# LogicLab.net
KiCad netlist of a schematic drawn in EAGLE
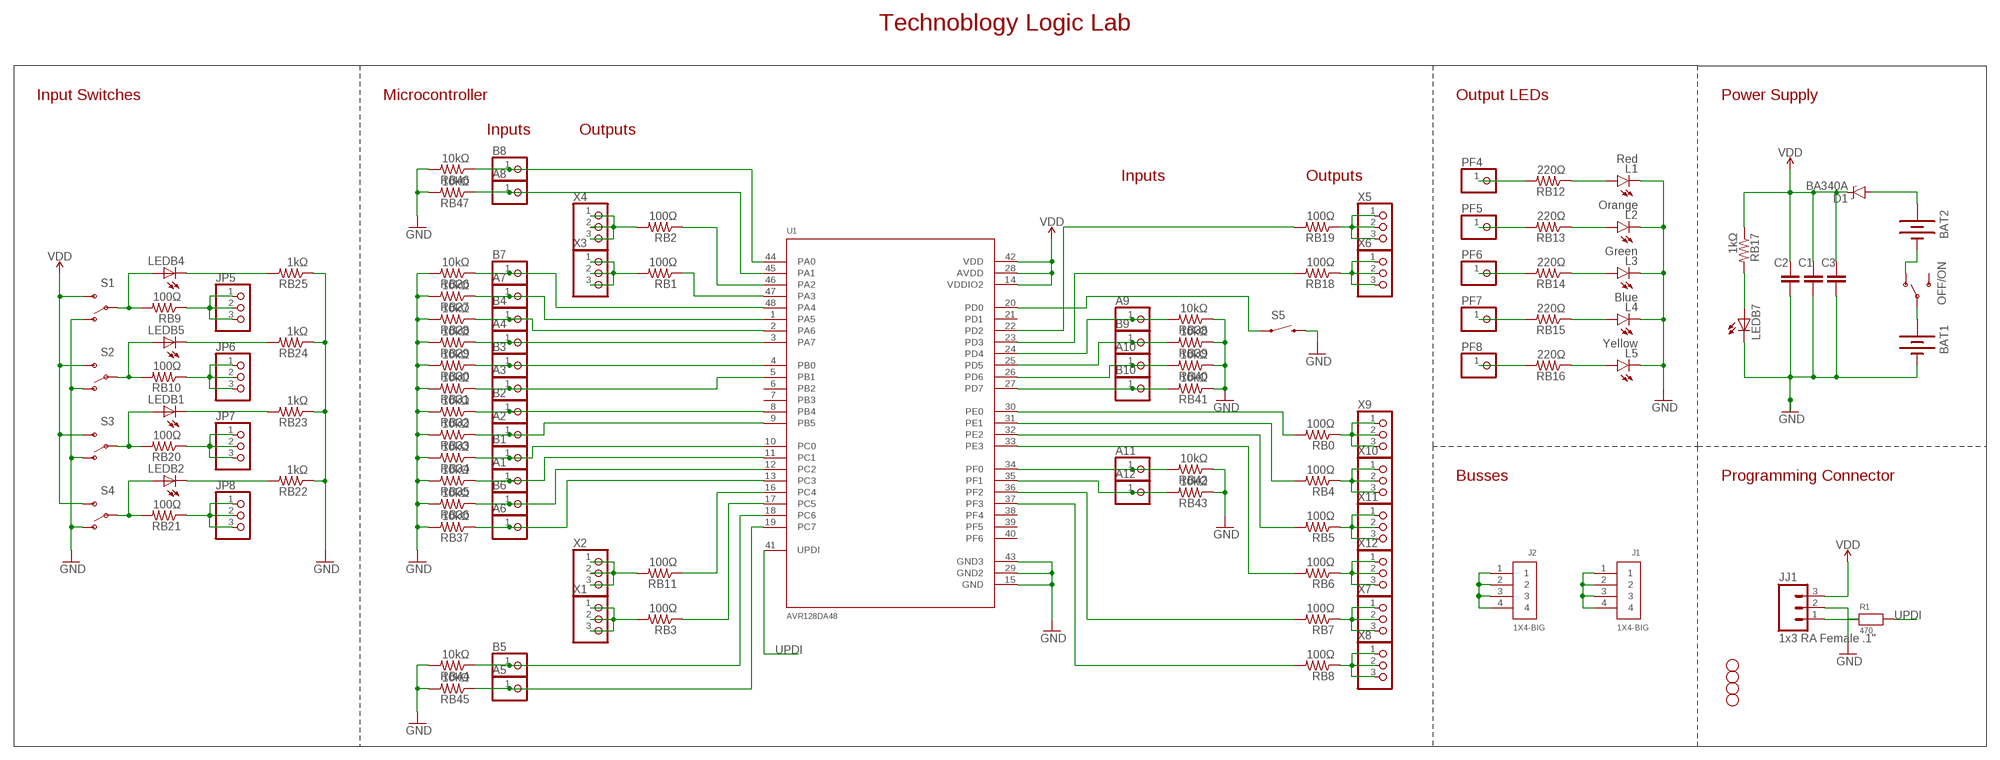
[diagram p0: schematic, sheet 1]

(export (version "E")
  (design (tool "Eeschema 10.0.6"))
  (components
    (comp (ref "A1")
      (value "PINHD-1X1")
      (footprint "eagle-import:1X01")
      (libsource (lib "eagle-import") (part "PINHD-1X1"))
    )
    (comp (ref "A2")
      (value "PINHD-1X1")
      (footprint "eagle-import:1X01")
      (libsource (lib "eagle-import") (part "PINHD-1X1"))
    )
    (comp (ref "A3")
      (value "PINHD-1X1")
      (footprint "eagle-import:1X01")
      (libsource (lib "eagle-import") (part "PINHD-1X1"))
    )
    (comp (ref "A4")
      (value "PINHD-1X1")
      (footprint "eagle-import:1X01")
      (libsource (lib "eagle-import") (part "PINHD-1X1"))
    )
    (comp (ref "A5")
      (value "PINHD-1X1")
      (footprint "eagle-import:1X01")
      (libsource (lib "eagle-import") (part "PINHD-1X1"))
    )
    (comp (ref "A6")
      (value "PINHD-1X1")
      (footprint "eagle-import:1X01")
      (libsource (lib "eagle-import") (part "PINHD-1X1"))
    )
    (comp (ref "A7")
      (value "PINHD-1X1")
      (footprint "eagle-import:1X01")
      (libsource (lib "eagle-import") (part "PINHD-1X1"))
    )
    (comp (ref "A8")
      (value "PINHD-1X1")
      (footprint "eagle-import:1X01")
      (libsource (lib "eagle-import") (part "PINHD-1X1"))
    )
    (comp (ref "A9")
      (value "PINHD-1X1")
      (footprint "eagle-import:1X01")
      (libsource (lib "eagle-import") (part "PINHD-1X1"))
    )
    (comp (ref "A10")
      (value "PINHD-1X1")
      (footprint "eagle-import:1X01")
      (libsource (lib "eagle-import") (part "PINHD-1X1"))
    )
    (comp (ref "A11")
      (value "PINHD-1X1")
      (footprint "eagle-import:1X01")
      (libsource (lib "eagle-import") (part "PINHD-1X1"))
    )
    (comp (ref "A12")
      (value "PINHD-1X1")
      (footprint "eagle-import:1X01")
      (libsource (lib "eagle-import") (part "PINHD-1X1"))
    )
    (comp (ref "B1")
      (value "PINHD-1X1")
      (footprint "eagle-import:1X01")
      (libsource (lib "eagle-import") (part "PINHD-1X1"))
    )
    (comp (ref "B2")
      (value "PINHD-1X1")
      (footprint "eagle-import:1X01")
      (libsource (lib "eagle-import") (part "PINHD-1X1"))
    )
    (comp (ref "B3")
      (value "PINHD-1X1")
      (footprint "eagle-import:1X01")
      (libsource (lib "eagle-import") (part "PINHD-1X1"))
    )
    (comp (ref "B4")
      (value "PINHD-1X1")
      (footprint "eagle-import:1X01")
      (libsource (lib "eagle-import") (part "PINHD-1X1"))
    )
    (comp (ref "B5")
      (value "PINHD-1X1")
      (footprint "eagle-import:1X01")
      (libsource (lib "eagle-import") (part "PINHD-1X1"))
    )
    (comp (ref "B6")
      (value "PINHD-1X1")
      (footprint "eagle-import:1X01")
      (libsource (lib "eagle-import") (part "PINHD-1X1"))
    )
    (comp (ref "B7")
      (value "PINHD-1X1")
      (footprint "eagle-import:1X01")
      (libsource (lib "eagle-import") (part "PINHD-1X1"))
    )
    (comp (ref "B8")
      (value "PINHD-1X1")
      (footprint "eagle-import:1X01")
      (libsource (lib "eagle-import") (part "PINHD-1X1"))
    )
    (comp (ref "B9")
      (value "PINHD-1X1")
      (footprint "eagle-import:1X01")
      (libsource (lib "eagle-import") (part "PINHD-1X1"))
    )
    (comp (ref "B10")
      (value "PINHD-1X1")
      (footprint "eagle-import:1X01")
      (libsource (lib "eagle-import") (part "PINHD-1X1"))
    )
    (comp (ref "BAT1")
      (value "BATTERYAAA-KIT")
      (footprint "eagle-import:BATTERY-AAA-KIT")
      (libsource (lib "eagle-import") (part "BATTERYAAA-KIT"))
    )
    (comp (ref "BAT2")
      (value "BATTERYAAA-KIT")
      (footprint "eagle-import:BATTERY-AAA-KIT")
      (libsource (lib "eagle-import") (part "BATTERYAAA-KIT"))
    )
    (comp (ref "C1")
      (value "100n")
      (footprint "eagle-import:0805")
      (libsource (lib "eagle-import") (part "CAP0805"))
    )
    (comp (ref "C2")
      (value "100n")
      (footprint "eagle-import:0805")
      (libsource (lib "eagle-import") (part "CAP0805"))
    )
    (comp (ref "C3")
      (value "10uF")
      (footprint "eagle-import:0805")
      (libsource (lib "eagle-import") (part "CAP0805"))
    )
    (comp (ref "D1")
      (value "BA340A")
      (footprint "eagle-import:SMA-DIODE")
      (libsource (lib "eagle-import") (part "B340A"))
    )
    (comp (ref "J1")
      (value "1X4-BIG")
      (footprint "eagle-import:1X04-BIG")
      (libsource (lib "eagle-import") (part "1X4-BIG"))
    )
    (comp (ref "J2")
      (value "1X4-BIG")
      (footprint "eagle-import:1X04-BIG")
      (libsource (lib "eagle-import") (part "1X4-BIG"))
    )
    (comp (ref "JJ1")
      (value "1x3 RA Female .1\"")
      (footprint "eagle-import:1X03_SMD_RA_FEMALE")
      (libsource (lib "eagle-import") (part "M03SMD_RA_FEMALE"))
    )
    (comp (ref "JP1")
      (value "STAND-OFF")
      (footprint "eagle-import:STAND-OFF")
      (libsource (lib "eagle-import") (part "STAND-OFF"))
    )
    (comp (ref "JP2")
      (value "STAND-OFF")
      (footprint "eagle-import:STAND-OFF")
      (libsource (lib "eagle-import") (part "STAND-OFF"))
    )
    (comp (ref "JP3")
      (value "STAND-OFF")
      (footprint "eagle-import:STAND-OFF")
      (libsource (lib "eagle-import") (part "STAND-OFF"))
    )
    (comp (ref "JP4")
      (value "STAND-OFF")
      (footprint "eagle-import:STAND-OFF")
      (libsource (lib "eagle-import") (part "STAND-OFF"))
    )
    (comp (ref "JP5")
      (value "PINHD-1X3")
      (footprint "eagle-import:1X03")
      (libsource (lib "eagle-import") (part "PINHD-1X3"))
    )
    (comp (ref "JP6")
      (value "PINHD-1X3")
      (footprint "eagle-import:1X03")
      (libsource (lib "eagle-import") (part "PINHD-1X3"))
    )
    (comp (ref "JP7")
      (value "PINHD-1X3")
      (footprint "eagle-import:1X03")
      (libsource (lib "eagle-import") (part "PINHD-1X3"))
    )
    (comp (ref "JP8")
      (value "PINHD-1X3")
      (footprint "eagle-import:1X03")
      (libsource (lib "eagle-import") (part "PINHD-1X3"))
    )
    (comp (ref "L1")
      (value "Red")
      (footprint "eagle-import:LED5MM")
      (libsource (lib "eagle-import") (part "LED5MM"))
    )
    (comp (ref "L2")
      (value "Orange")
      (footprint "eagle-import:LED5MM")
      (libsource (lib "eagle-import") (part "LED5MM"))
    )
    (comp (ref "L3")
      (value "Green")
      (footprint "eagle-import:LED5MM")
      (libsource (lib "eagle-import") (part "LED5MM"))
    )
    (comp (ref "L4")
      (value "Blue")
      (footprint "eagle-import:LED5MM")
      (libsource (lib "eagle-import") (part "LED5MM"))
    )
    (comp (ref "L5")
      (value "Yellow")
      (footprint "eagle-import:LED5MM")
      (libsource (lib "eagle-import") (part "LED5MM"))
    )
    (comp (ref "LEDB1")
      (value "LEDCHIPLED_0805")
      (footprint "eagle-import:CHIPLED_0805")
      (libsource (lib "eagle-import") (part "LEDCHIPLED_0805"))
    )
    (comp (ref "LEDB2")
      (value "LEDCHIPLED_0805")
      (footprint "eagle-import:CHIPLED_0805")
      (libsource (lib "eagle-import") (part "LEDCHIPLED_0805"))
    )
    (comp (ref "LEDB4")
      (value "LEDCHIPLED_0805")
      (footprint "eagle-import:CHIPLED_0805")
      (libsource (lib "eagle-import") (part "LEDCHIPLED_0805"))
    )
    (comp (ref "LEDB5")
      (value "LEDCHIPLED_0805")
      (footprint "eagle-import:CHIPLED_0805")
      (libsource (lib "eagle-import") (part "LEDCHIPLED_0805"))
    )
    (comp (ref "LEDB7")
      (value "LEDCHIPLED_0805")
      (footprint "eagle-import:CHIPLED_0805")
      (libsource (lib "eagle-import") (part "LEDCHIPLED_0805"))
    )
    (comp (ref "OFF/ON")
      (value "SWITCH-SPDTKIT")
      (footprint "eagle-import:SWITCH-SPDT_KIT")
      (libsource (lib "eagle-import") (part "SWITCH-SPDTKIT"))
    )
    (comp (ref "PF4")
      (value "PINHD-1X1")
      (footprint "eagle-import:1X01")
      (libsource (lib "eagle-import") (part "PINHD-1X1"))
    )
    (comp (ref "PF5")
      (value "PINHD-1X1")
      (footprint "eagle-import:1X01")
      (libsource (lib "eagle-import") (part "PINHD-1X1"))
    )
    (comp (ref "PF6")
      (value "PINHD-1X1")
      (footprint "eagle-import:1X01")
      (libsource (lib "eagle-import") (part "PINHD-1X1"))
    )
    (comp (ref "PF7")
      (value "PINHD-1X1")
      (footprint "eagle-import:1X01")
      (libsource (lib "eagle-import") (part "PINHD-1X1"))
    )
    (comp (ref "PF8")
      (value "PINHD-1X1")
      (footprint "eagle-import:1X01")
      (libsource (lib "eagle-import") (part "PINHD-1X1"))
    )
    (comp (ref "R1")
      (value "470")
      (footprint "eagle-import:_0805MP")
      (libsource (lib "eagle-import") (part "RESISTOR_0805MP"))
    )
    (comp (ref "RB0")
      (value "100Ω")
      (footprint "eagle-import:0805")
      (libsource (lib "eagle-import") (part "RESISTOR0805-RES"))
    )
    (comp (ref "RB1")
      (value "100Ω")
      (footprint "eagle-import:0805")
      (libsource (lib "eagle-import") (part "RESISTOR0805-RES"))
    )
    (comp (ref "RB2")
      (value "100Ω")
      (footprint "eagle-import:0805")
      (libsource (lib "eagle-import") (part "RESISTOR0805-RES"))
    )
    (comp (ref "RB3")
      (value "100Ω")
      (footprint "eagle-import:0805")
      (libsource (lib "eagle-import") (part "RESISTOR0805-RES"))
    )
    (comp (ref "RB4")
      (value "100Ω")
      (footprint "eagle-import:0805")
      (libsource (lib "eagle-import") (part "RESISTOR0805-RES"))
    )
    (comp (ref "RB5")
      (value "100Ω")
      (footprint "eagle-import:0805")
      (libsource (lib "eagle-import") (part "RESISTOR0805-RES"))
    )
    (comp (ref "RB6")
      (value "100Ω")
      (footprint "eagle-import:0805")
      (libsource (lib "eagle-import") (part "RESISTOR0805-RES"))
    )
    (comp (ref "RB7")
      (value "100Ω")
      (footprint "eagle-import:0805")
      (libsource (lib "eagle-import") (part "RESISTOR0805-RES"))
    )
    (comp (ref "RB8")
      (value "100Ω")
      (footprint "eagle-import:0805")
      (libsource (lib "eagle-import") (part "RESISTOR0805-RES"))
    )
    (comp (ref "RB9")
      (value "100Ω")
      (footprint "eagle-import:0805")
      (libsource (lib "eagle-import") (part "RESISTOR0805-RES"))
    )
    (comp (ref "RB10")
      (value "100Ω")
      (footprint "eagle-import:0805")
      (libsource (lib "eagle-import") (part "RESISTOR0805-RES"))
    )
    (comp (ref "RB11")
      (value "100Ω")
      (footprint "eagle-import:0805")
      (libsource (lib "eagle-import") (part "RESISTOR0805-RES"))
    )
    (comp (ref "RB12")
      (value "220Ω")
      (footprint "eagle-import:0805")
      (libsource (lib "eagle-import") (part "RESISTOR0805-RES"))
    )
    (comp (ref "RB13")
      (value "220Ω")
      (footprint "eagle-import:0805")
      (libsource (lib "eagle-import") (part "RESISTOR0805-RES"))
    )
    (comp (ref "RB14")
      (value "220Ω")
      (footprint "eagle-import:0805")
      (libsource (lib "eagle-import") (part "RESISTOR0805-RES"))
    )
    (comp (ref "RB15")
      (value "220Ω")
      (footprint "eagle-import:0805")
      (libsource (lib "eagle-import") (part "RESISTOR0805-RES"))
    )
    (comp (ref "RB16")
      (value "220Ω")
      (footprint "eagle-import:0805")
      (libsource (lib "eagle-import") (part "RESISTOR0805-RES"))
    )
    (comp (ref "RB17")
      (value "1kΩ")
      (footprint "eagle-import:0805")
      (libsource (lib "eagle-import") (part "RESISTOR0805-RES"))
    )
    (comp (ref "RB18")
      (value "100Ω")
      (footprint "eagle-import:0805")
      (libsource (lib "eagle-import") (part "RESISTOR0805-RES"))
    )
    (comp (ref "RB19")
      (value "100Ω")
      (footprint "eagle-import:0805")
      (libsource (lib "eagle-import") (part "RESISTOR0805-RES"))
    )
    (comp (ref "RB20")
      (value "100Ω")
      (footprint "eagle-import:0805")
      (libsource (lib "eagle-import") (part "RESISTOR0805-RES"))
    )
    (comp (ref "RB21")
      (value "100Ω")
      (footprint "eagle-import:0805")
      (libsource (lib "eagle-import") (part "RESISTOR0805-RES"))
    )
    (comp (ref "RB22")
      (value "1kΩ")
      (footprint "eagle-import:0805")
      (libsource (lib "eagle-import") (part "RESISTOR0805-RES"))
    )
    (comp (ref "RB23")
      (value "1kΩ")
      (footprint "eagle-import:0805")
      (libsource (lib "eagle-import") (part "RESISTOR0805-RES"))
    )
    (comp (ref "RB24")
      (value "1kΩ")
      (footprint "eagle-import:0805")
      (libsource (lib "eagle-import") (part "RESISTOR0805-RES"))
    )
    (comp (ref "RB25")
      (value "1kΩ")
      (footprint "eagle-import:0805")
      (libsource (lib "eagle-import") (part "RESISTOR0805-RES"))
    )
    (comp (ref "RB26")
      (value "10kΩ")
      (footprint "eagle-import:0805")
      (libsource (lib "eagle-import") (part "RESISTOR0805-RES"))
    )
    (comp (ref "RB27")
      (value "10kΩ")
      (footprint "eagle-import:0805")
      (libsource (lib "eagle-import") (part "RESISTOR0805-RES"))
    )
    (comp (ref "RB28")
      (value "10kΩ")
      (footprint "eagle-import:0805")
      (libsource (lib "eagle-import") (part "RESISTOR0805-RES"))
    )
    (comp (ref "RB29")
      (value "10kΩ")
      (footprint "eagle-import:0805")
      (libsource (lib "eagle-import") (part "RESISTOR0805-RES"))
    )
    (comp (ref "RB30")
      (value "10kΩ")
      (footprint "eagle-import:0805")
      (libsource (lib "eagle-import") (part "RESISTOR0805-RES"))
    )
    (comp (ref "RB31")
      (value "10kΩ")
      (footprint "eagle-import:0805")
      (libsource (lib "eagle-import") (part "RESISTOR0805-RES"))
    )
    (comp (ref "RB32")
      (value "10kΩ")
      (footprint "eagle-import:0805")
      (libsource (lib "eagle-import") (part "RESISTOR0805-RES"))
    )
    (comp (ref "RB33")
      (value "10kΩ")
      (footprint "eagle-import:0805")
      (libsource (lib "eagle-import") (part "RESISTOR0805-RES"))
    )
    (comp (ref "RB34")
      (value "10kΩ")
      (footprint "eagle-import:0805")
      (libsource (lib "eagle-import") (part "RESISTOR0805-RES"))
    )
    (comp (ref "RB35")
      (value "10kΩ")
      (footprint "eagle-import:0805")
      (libsource (lib "eagle-import") (part "RESISTOR0805-RES"))
    )
    (comp (ref "RB36")
      (value "10kΩ")
      (footprint "eagle-import:0805")
      (libsource (lib "eagle-import") (part "RESISTOR0805-RES"))
    )
    (comp (ref "RB37")
      (value "10kΩ")
      (footprint "eagle-import:0805")
      (libsource (lib "eagle-import") (part "RESISTOR0805-RES"))
    )
    (comp (ref "RB38")
      (value "10kΩ")
      (footprint "eagle-import:0805")
      (libsource (lib "eagle-import") (part "RESISTOR0805-RES"))
    )
    (comp (ref "RB39")
      (value "10kΩ")
      (footprint "eagle-import:0805")
      (libsource (lib "eagle-import") (part "RESISTOR0805-RES"))
    )
    (comp (ref "RB40")
      (value "10kΩ")
      (footprint "eagle-import:0805")
      (libsource (lib "eagle-import") (part "RESISTOR0805-RES"))
    )
    (comp (ref "RB41")
      (value "10kΩ")
      (footprint "eagle-import:0805")
      (libsource (lib "eagle-import") (part "RESISTOR0805-RES"))
    )
    (comp (ref "RB42")
      (value "10kΩ")
      (footprint "eagle-import:0805")
      (libsource (lib "eagle-import") (part "RESISTOR0805-RES"))
    )
    (comp (ref "RB43")
      (value "10kΩ")
      (footprint "eagle-import:0805")
      (libsource (lib "eagle-import") (part "RESISTOR0805-RES"))
    )
    (comp (ref "RB44")
      (value "10kΩ")
      (footprint "eagle-import:0805")
      (libsource (lib "eagle-import") (part "RESISTOR0805-RES"))
    )
    (comp (ref "RB45")
      (value "10kΩ")
      (footprint "eagle-import:0805")
      (libsource (lib "eagle-import") (part "RESISTOR0805-RES"))
    )
    (comp (ref "RB46")
      (value "10kΩ")
      (footprint "eagle-import:0805")
      (libsource (lib "eagle-import") (part "RESISTOR0805-RES"))
    )
    (comp (ref "RB47")
      (value "10kΩ")
      (footprint "eagle-import:0805")
      (libsource (lib "eagle-import") (part "RESISTOR0805-RES"))
    )
    (comp (ref "S1")
      (value "SWITCH-SPDTKIT")
      (footprint "eagle-import:SWITCH-SPDT_KIT")
      (libsource (lib "eagle-import") (part "SWITCH-SPDTKIT"))
    )
    (comp (ref "S2")
      (value "SWITCH-SPDTKIT")
      (footprint "eagle-import:SWITCH-SPDT_KIT")
      (libsource (lib "eagle-import") (part "SWITCH-SPDTKIT"))
    )
    (comp (ref "S3")
      (value "SWITCH-SPDTKIT")
      (footprint "eagle-import:SWITCH-SPDT_KIT")
      (libsource (lib "eagle-import") (part "SWITCH-SPDTKIT"))
    )
    (comp (ref "S4")
      (value "SWITCH-SPDTKIT")
      (footprint "eagle-import:SWITCH-SPDT_KIT")
      (libsource (lib "eagle-import") (part "SWITCH-SPDTKIT"))
    )
    (comp (ref "S5")
      (value "SWITCH-MOMENTARY-2SMD-4.6X2.8MM")
      (footprint "eagle-import:TACTILE_SWITCH_SMD_4.6X2.8MM")
      (libsource (lib "eagle-import") (part "SWITCH-MOMENTARY-2SMD-4.6X2.8MM"))
    )
    (comp (ref "U1")
      (value "AVR128DA48")
      (footprint "eagle-import:LQFP48")
      (fields (field (name "MANF") "NXP"))
      (libsource (lib "eagle-import") (part "AVR128DB48"))
    )
    (comp (ref "X1")
      (value "PINHD-1X3")
      (footprint "eagle-import:1X03")
      (libsource (lib "eagle-import") (part "PINHD-1X3"))
    )
    (comp (ref "X2")
      (value "PINHD-1X3")
      (footprint "eagle-import:1X03")
      (libsource (lib "eagle-import") (part "PINHD-1X3"))
    )
    (comp (ref "X3")
      (value "PINHD-1X3")
      (footprint "eagle-import:1X03")
      (libsource (lib "eagle-import") (part "PINHD-1X3"))
    )
    (comp (ref "X4")
      (value "PINHD-1X3")
      (footprint "eagle-import:1X03")
      (libsource (lib "eagle-import") (part "PINHD-1X3"))
    )
    (comp (ref "X5")
      (value "PINHD-1X3")
      (footprint "eagle-import:1X03")
      (libsource (lib "eagle-import") (part "PINHD-1X3"))
    )
    (comp (ref "X6")
      (value "PINHD-1X3")
      (footprint "eagle-import:1X03")
      (libsource (lib "eagle-import") (part "PINHD-1X3"))
    )
    (comp (ref "X7")
      (value "PINHD-1X3")
      (footprint "eagle-import:1X03")
      (libsource (lib "eagle-import") (part "PINHD-1X3"))
    )
    (comp (ref "X8")
      (value "PINHD-1X3")
      (footprint "eagle-import:1X03")
      (libsource (lib "eagle-import") (part "PINHD-1X3"))
    )
    (comp (ref "X9")
      (value "PINHD-1X3")
      (footprint "eagle-import:1X03")
      (libsource (lib "eagle-import") (part "PINHD-1X3"))
    )
    (comp (ref "X10")
      (value "PINHD-1X3")
      (footprint "eagle-import:1X03")
      (libsource (lib "eagle-import") (part "PINHD-1X3"))
    )
    (comp (ref "X11")
      (value "PINHD-1X3")
      (footprint "eagle-import:1X03")
      (libsource (lib "eagle-import") (part "PINHD-1X3"))
    )
    (comp (ref "X12")
      (value "PINHD-1X3")
      (footprint "eagle-import:1X03")
      (libsource (lib "eagle-import") (part "PINHD-1X3"))
    )
  )
  (nets
    (net (code "1") (name "/UPDI") (class "Default")
      (node (ref "R1") (pin "2") (pinfunction "2_2") (pintype "passive"))
      (node (ref "U1") (pin "41") (pinfunction "UPDI_41") (pintype "bidirectional"))
    )
    (net (code "2") (name "GND") (class "Default")
      (node (ref "BAT1") (pin "GND@1") (pinfunction "-_GND@1") (pintype "power_in"))
      (node (ref "C1") (pin "2") (pinfunction "2_2") (pintype "passive"))
      (node (ref "C2") (pin "2") (pinfunction "2_2") (pintype "passive"))
      (node (ref "C3") (pin "2") (pinfunction "2_2") (pintype "passive"))
      (node (ref "JJ1") (pin "2") (pinfunction "2_2") (pintype "passive"))
      (node (ref "L1") (pin "K") (pinfunction "C_K") (pintype "passive"))
      (node (ref "L2") (pin "K") (pinfunction "C_K") (pintype "passive"))
      (node (ref "L3") (pin "K") (pinfunction "C_K") (pintype "passive"))
      (node (ref "L4") (pin "K") (pinfunction "C_K") (pintype "passive"))
      (node (ref "L5") (pin "K") (pinfunction "C_K") (pintype "passive"))
      (node (ref "LEDB7") (pin "C") (pinfunction "C_C") (pintype "passive"))
      (node (ref "RB22") (pin "1") (pinfunction "1_1") (pintype "passive"))
      (node (ref "RB23") (pin "1") (pinfunction "1_1") (pintype "passive"))
      (node (ref "RB24") (pin "1") (pinfunction "1_1") (pintype "passive"))
      (node (ref "RB25") (pin "1") (pinfunction "1_1") (pintype "passive"))
      (node (ref "RB26") (pin "2") (pinfunction "2_2") (pintype "passive"))
      (node (ref "RB27") (pin "2") (pinfunction "2_2") (pintype "passive"))
      (node (ref "RB28") (pin "2") (pinfunction "2_2") (pintype "passive"))
      (node (ref "RB29") (pin "2") (pinfunction "2_2") (pintype "passive"))
      (node (ref "RB30") (pin "2") (pinfunction "2_2") (pintype "passive"))
      (node (ref "RB31") (pin "2") (pinfunction "2_2") (pintype "passive"))
      (node (ref "RB32") (pin "2") (pinfunction "2_2") (pintype "passive"))
      (node (ref "RB33") (pin "2") (pinfunction "2_2") (pintype "passive"))
      (node (ref "RB34") (pin "2") (pinfunction "2_2") (pintype "passive"))
      (node (ref "RB35") (pin "2") (pinfunction "2_2") (pintype "passive"))
      (node (ref "RB36") (pin "2") (pinfunction "2_2") (pintype "passive"))
      (node (ref "RB37") (pin "2") (pinfunction "2_2") (pintype "passive"))
      (node (ref "RB38") (pin "1") (pinfunction "1_1") (pintype "passive"))
      (node (ref "RB39") (pin "1") (pinfunction "1_1") (pintype "passive"))
      (node (ref "RB40") (pin "1") (pinfunction "1_1") (pintype "passive"))
      (node (ref "RB41") (pin "1") (pinfunction "1_1") (pintype "passive"))
      (node (ref "RB42") (pin "1") (pinfunction "1_1") (pintype "passive"))
      (node (ref "RB43") (pin "1") (pinfunction "1_1") (pintype "passive"))
      (node (ref "RB44") (pin "2") (pinfunction "2_2") (pintype "passive"))
      (node (ref "RB45") (pin "2") (pinfunction "2_2") (pintype "passive"))
      (node (ref "RB46") (pin "2") (pinfunction "2_2") (pintype "passive"))
      (node (ref "RB47") (pin "2") (pinfunction "2_2") (pintype "passive"))
      (node (ref "S1") (pin "1") (pinfunction "O_1") (pintype "passive"))
      (node (ref "S2") (pin "1") (pinfunction "O_1") (pintype "passive"))
      (node (ref "S3") (pin "1") (pinfunction "O_1") (pintype "passive"))
      (node (ref "S4") (pin "1") (pinfunction "O_1") (pintype "passive"))
      (node (ref "S5") (pin "3") (pinfunction "2_3") (pintype "passive"))
      (node (ref "S5") (pin "4") (pinfunction "2_4") (pintype "passive"))
      (node (ref "U1") (pin "15") (pinfunction "GND_15") (pintype "power_in"))
      (node (ref "U1") (pin "29") (pinfunction "GND2_29") (pintype "power_in"))
      (node (ref "U1") (pin "43") (pinfunction "GND3_43") (pintype "power_in"))
    )
    (net (code "3") (name "Net-(BAT1-+)") (class "Default")
      (node (ref "BAT1") (pin "PWR@1") (pinfunction "+_PWR@1") (pintype "power_in"))
      (node (ref "OFF/ON") (pin "2") (pinfunction "P_2") (pintype "passive"))
    )
    (net (code "4") (name "Net-(BAT2-+)") (class "Default")
      (node (ref "BAT2") (pin "PWR@1") (pinfunction "+_PWR@1") (pintype "power_in"))
      (node (ref "D1") (pin "A") (pinfunction "A_A") (pintype "passive"))
    )
    (net (code "5") (name "Net-(BAT2--)") (class "Default")
      (node (ref "BAT2") (pin "GND@1") (pinfunction "-_GND@1") (pintype "power_in"))
      (node (ref "OFF/ON") (pin "1") (pinfunction "O_1") (pintype "passive"))
    )
    (net (code "6") (name "Net-(J1-Pad1)") (class "Default")
      (node (ref "J1") (pin "1") (pinfunction "1_1") (pintype "bidirectional"))
      (node (ref "J1") (pin "2") (pinfunction "2_2") (pintype "bidirectional"))
      (node (ref "J1") (pin "3") (pinfunction "3_3") (pintype "bidirectional"))
      (node (ref "J1") (pin "4") (pinfunction "4_4") (pintype "bidirectional"))
    )
    (net (code "7") (name "Net-(J2-Pad1)") (class "Default")
      (node (ref "J2") (pin "1") (pinfunction "1_1") (pintype "bidirectional"))
      (node (ref "J2") (pin "2") (pinfunction "2_2") (pintype "bidirectional"))
      (node (ref "J2") (pin "3") (pinfunction "3_3") (pintype "bidirectional"))
      (node (ref "J2") (pin "4") (pinfunction "4_4") (pintype "bidirectional"))
    )
    (net (code "8") (name "Net-(JJ1-Pad1)") (class "Default")
      (node (ref "JJ1") (pin "1") (pinfunction "1_1") (pintype "passive"))
      (node (ref "R1") (pin "1") (pinfunction "1_1") (pintype "passive"))
    )
    (net (code "9") (name "Net-(JP5-Pad1)") (class "Default")
      (node (ref "JP5") (pin "1") (pinfunction "1_1") (pintype "passive"))
      (node (ref "JP5") (pin "2") (pinfunction "2_2") (pintype "passive"))
      (node (ref "JP5") (pin "3") (pinfunction "3_3") (pintype "passive"))
      (node (ref "RB9") (pin "1") (pinfunction "1_1") (pintype "passive"))
    )
    (net (code "10") (name "Net-(JP6-Pad1)") (class "Default")
      (node (ref "JP6") (pin "1") (pinfunction "1_1") (pintype "passive"))
      (node (ref "JP6") (pin "2") (pinfunction "2_2") (pintype "passive"))
      (node (ref "JP6") (pin "3") (pinfunction "3_3") (pintype "passive"))
      (node (ref "RB10") (pin "1") (pinfunction "1_1") (pintype "passive"))
    )
    (net (code "11") (name "Net-(JP7-Pad1)") (class "Default")
      (node (ref "JP7") (pin "1") (pinfunction "1_1") (pintype "passive"))
      (node (ref "JP7") (pin "2") (pinfunction "2_2") (pintype "passive"))
      (node (ref "JP7") (pin "3") (pinfunction "3_3") (pintype "passive"))
      (node (ref "RB20") (pin "1") (pinfunction "1_1") (pintype "passive"))
    )
    (net (code "12") (name "Net-(JP8-Pad1)") (class "Default")
      (node (ref "JP8") (pin "1") (pinfunction "1_1") (pintype "passive"))
      (node (ref "JP8") (pin "2") (pinfunction "2_2") (pintype "passive"))
      (node (ref "JP8") (pin "3") (pinfunction "3_3") (pintype "passive"))
      (node (ref "RB21") (pin "1") (pinfunction "1_1") (pintype "passive"))
    )
    (net (code "13") (name "Net-(L1-PadA)") (class "Default")
      (node (ref "L1") (pin "A") (pinfunction "A_A") (pintype "passive"))
      (node (ref "RB12") (pin "1") (pinfunction "1_1") (pintype "passive"))
    )
    (net (code "14") (name "Net-(L2-PadA)") (class "Default")
      (node (ref "L2") (pin "A") (pinfunction "A_A") (pintype "passive"))
      (node (ref "RB13") (pin "1") (pinfunction "1_1") (pintype "passive"))
    )
    (net (code "15") (name "Net-(L3-PadA)") (class "Default")
      (node (ref "L3") (pin "A") (pinfunction "A_A") (pintype "passive"))
      (node (ref "RB14") (pin "1") (pinfunction "1_1") (pintype "passive"))
    )
    (net (code "16") (name "Net-(L4-PadA)") (class "Default")
      (node (ref "L4") (pin "A") (pinfunction "A_A") (pintype "passive"))
      (node (ref "RB15") (pin "1") (pinfunction "1_1") (pintype "passive"))
    )
    (net (code "17") (name "Net-(L5-PadA)") (class "Default")
      (node (ref "L5") (pin "A") (pinfunction "A_A") (pintype "passive"))
      (node (ref "RB16") (pin "1") (pinfunction "1_1") (pintype "passive"))
    )
    (net (code "18") (name "Net-(LEDB1-PadC)") (class "Default")
      (node (ref "LEDB1") (pin "C") (pinfunction "C_C") (pintype "passive"))
      (node (ref "RB23") (pin "2") (pinfunction "2_2") (pintype "passive"))
    )
    (net (code "19") (name "Net-(LEDB2-PadC)") (class "Default")
      (node (ref "LEDB2") (pin "C") (pinfunction "C_C") (pintype "passive"))
      (node (ref "RB22") (pin "2") (pinfunction "2_2") (pintype "passive"))
    )
    (net (code "20") (name "Net-(LEDB4-PadC)") (class "Default")
      (node (ref "LEDB4") (pin "C") (pinfunction "C_C") (pintype "passive"))
      (node (ref "RB25") (pin "2") (pinfunction "2_2") (pintype "passive"))
    )
    (net (code "21") (name "Net-(LEDB5-PadC)") (class "Default")
      (node (ref "LEDB5") (pin "C") (pinfunction "C_C") (pintype "passive"))
      (node (ref "RB24") (pin "2") (pinfunction "2_2") (pintype "passive"))
    )
    (net (code "22") (name "Net-(LEDB7-PadA)") (class "Default")
      (node (ref "LEDB7") (pin "A") (pinfunction "A_A") (pintype "passive"))
      (node (ref "RB17") (pin "2") (pinfunction "2_2") (pintype "passive"))
    )
    (net (code "23") (name "Net-(PF4-Pad1)") (class "Default")
      (node (ref "PF4") (pin "1") (pinfunction "1_1") (pintype "passive"))
      (node (ref "RB12") (pin "2") (pinfunction "2_2") (pintype "passive"))
    )
    (net (code "24") (name "Net-(PF5-Pad1)") (class "Default")
      (node (ref "PF5") (pin "1") (pinfunction "1_1") (pintype "passive"))
      (node (ref "RB13") (pin "2") (pinfunction "2_2") (pintype "passive"))
    )
    (net (code "25") (name "Net-(PF6-Pad1)") (class "Default")
      (node (ref "PF6") (pin "1") (pinfunction "1_1") (pintype "passive"))
      (node (ref "RB14") (pin "2") (pinfunction "2_2") (pintype "passive"))
    )
    (net (code "26") (name "Net-(PF7-Pad1)") (class "Default")
      (node (ref "PF7") (pin "1") (pinfunction "1_1") (pintype "passive"))
      (node (ref "RB15") (pin "2") (pinfunction "2_2") (pintype "passive"))
    )
    (net (code "27") (name "Net-(PF8-Pad1)") (class "Default")
      (node (ref "PF8") (pin "1") (pinfunction "1_1") (pintype "passive"))
      (node (ref "RB16") (pin "2") (pinfunction "2_2") (pintype "passive"))
    )
    (net (code "28") (name "Net-(RB0-Pad1)") (class "Default")
      (node (ref "RB0") (pin "1") (pinfunction "1_1") (pintype "passive"))
      (node (ref "X9") (pin "1") (pinfunction "1_1") (pintype "passive"))
      (node (ref "X9") (pin "2") (pinfunction "2_2") (pintype "passive"))
      (node (ref "X9") (pin "3") (pinfunction "3_3") (pintype "passive"))
    )
    (net (code "29") (name "Net-(RB1-Pad2)") (class "Default")
      (node (ref "RB1") (pin "2") (pinfunction "2_2") (pintype "passive"))
      (node (ref "X3") (pin "1") (pinfunction "1_1") (pintype "passive"))
      (node (ref "X3") (pin "2") (pinfunction "2_2") (pintype "passive"))
      (node (ref "X3") (pin "3") (pinfunction "3_3") (pintype "passive"))
    )
    (net (code "30") (name "Net-(RB2-Pad2)") (class "Default")
      (node (ref "RB2") (pin "2") (pinfunction "2_2") (pintype "passive"))
      (node (ref "X4") (pin "1") (pinfunction "1_1") (pintype "passive"))
      (node (ref "X4") (pin "2") (pinfunction "2_2") (pintype "passive"))
      (node (ref "X4") (pin "3") (pinfunction "3_3") (pintype "passive"))
    )
    (net (code "31") (name "Net-(RB3-Pad2)") (class "Default")
      (node (ref "RB3") (pin "2") (pinfunction "2_2") (pintype "passive"))
      (node (ref "X1") (pin "1") (pinfunction "1_1") (pintype "passive"))
      (node (ref "X1") (pin "2") (pinfunction "2_2") (pintype "passive"))
      (node (ref "X1") (pin "3") (pinfunction "3_3") (pintype "passive"))
    )
    (net (code "32") (name "Net-(RB4-Pad1)") (class "Default")
      (node (ref "RB4") (pin "1") (pinfunction "1_1") (pintype "passive"))
      (node (ref "X10") (pin "1") (pinfunction "1_1") (pintype "passive"))
      (node (ref "X10") (pin "2") (pinfunction "2_2") (pintype "passive"))
      (node (ref "X10") (pin "3") (pinfunction "3_3") (pintype "passive"))
    )
    (net (code "33") (name "Net-(RB5-Pad1)") (class "Default")
      (node (ref "RB5") (pin "1") (pinfunction "1_1") (pintype "passive"))
      (node (ref "X11") (pin "1") (pinfunction "1_1") (pintype "passive"))
      (node (ref "X11") (pin "2") (pinfunction "2_2") (pintype "passive"))
      (node (ref "X11") (pin "3") (pinfunction "3_3") (pintype "passive"))
    )
    (net (code "34") (name "Net-(RB6-Pad1)") (class "Default")
      (node (ref "RB6") (pin "1") (pinfunction "1_1") (pintype "passive"))
      (node (ref "X12") (pin "1") (pinfunction "1_1") (pintype "passive"))
      (node (ref "X12") (pin "2") (pinfunction "2_2") (pintype "passive"))
      (node (ref "X12") (pin "3") (pinfunction "3_3") (pintype "passive"))
    )
    (net (code "35") (name "Net-(RB7-Pad1)") (class "Default")
      (node (ref "RB7") (pin "1") (pinfunction "1_1") (pintype "passive"))
      (node (ref "X7") (pin "1") (pinfunction "1_1") (pintype "passive"))
      (node (ref "X7") (pin "2") (pinfunction "2_2") (pintype "passive"))
      (node (ref "X7") (pin "3") (pinfunction "3_3") (pintype "passive"))
    )
    (net (code "36") (name "Net-(RB8-Pad1)") (class "Default")
      (node (ref "RB8") (pin "1") (pinfunction "1_1") (pintype "passive"))
      (node (ref "X8") (pin "1") (pinfunction "1_1") (pintype "passive"))
      (node (ref "X8") (pin "2") (pinfunction "2_2") (pintype "passive"))
      (node (ref "X8") (pin "3") (pinfunction "3_3") (pintype "passive"))
    )
    (net (code "37") (name "Net-(RB11-Pad2)") (class "Default")
      (node (ref "RB11") (pin "2") (pinfunction "2_2") (pintype "passive"))
      (node (ref "X2") (pin "1") (pinfunction "1_1") (pintype "passive"))
      (node (ref "X2") (pin "2") (pinfunction "2_2") (pintype "passive"))
      (node (ref "X2") (pin "3") (pinfunction "3_3") (pintype "passive"))
    )
    (net (code "38") (name "Net-(RB18-Pad1)") (class "Default")
      (node (ref "RB18") (pin "1") (pinfunction "1_1") (pintype "passive"))
      (node (ref "X6") (pin "1") (pinfunction "1_1") (pintype "passive"))
      (node (ref "X6") (pin "2") (pinfunction "2_2") (pintype "passive"))
      (node (ref "X6") (pin "3") (pinfunction "3_3") (pintype "passive"))
    )
    (net (code "39") (name "Net-(RB19-Pad1)") (class "Default")
      (node (ref "RB19") (pin "1") (pinfunction "1_1") (pintype "passive"))
      (node (ref "X5") (pin "1") (pinfunction "1_1") (pintype "passive"))
      (node (ref "X5") (pin "2") (pinfunction "2_2") (pintype "passive"))
      (node (ref "X5") (pin "3") (pinfunction "3_3") (pintype "passive"))
    )
    (net (code "40") (name "Net-(S1-P)") (class "Default")
      (node (ref "LEDB4") (pin "A") (pinfunction "A_A") (pintype "passive"))
      (node (ref "RB9") (pin "2") (pinfunction "2_2") (pintype "passive"))
      (node (ref "S1") (pin "2") (pinfunction "P_2") (pintype "passive"))
    )
    (net (code "41") (name "Net-(S2-P)") (class "Default")
      (node (ref "LEDB5") (pin "A") (pinfunction "A_A") (pintype "passive"))
      (node (ref "RB10") (pin "2") (pinfunction "2_2") (pintype "passive"))
      (node (ref "S2") (pin "2") (pinfunction "P_2") (pintype "passive"))
    )
    (net (code "42") (name "Net-(S3-P)") (class "Default")
      (node (ref "LEDB1") (pin "A") (pinfunction "A_A") (pintype "passive"))
      (node (ref "RB20") (pin "2") (pinfunction "2_2") (pintype "passive"))
      (node (ref "S3") (pin "2") (pinfunction "P_2") (pintype "passive"))
    )
    (net (code "43") (name "Net-(S4-P)") (class "Default")
      (node (ref "LEDB2") (pin "A") (pinfunction "A_A") (pintype "passive"))
      (node (ref "RB21") (pin "2") (pinfunction "2_2") (pintype "passive"))
      (node (ref "S4") (pin "2") (pinfunction "P_2") (pintype "passive"))
    )
    (net (code "44") (name "Net-(U1-PA0)") (class "Default")
      (node (ref "B8") (pin "1") (pinfunction "1_1") (pintype "passive"))
      (node (ref "RB46") (pin "1") (pinfunction "1_1") (pintype "passive"))
      (node (ref "U1") (pin "44") (pinfunction "PA0_44") (pintype "bidirectional"))
    )
    (net (code "45") (name "Net-(U1-PA1)") (class "Default")
      (node (ref "A8") (pin "1") (pinfunction "1_1") (pintype "passive"))
      (node (ref "RB47") (pin "1") (pinfunction "1_1") (pintype "passive"))
      (node (ref "U1") (pin "45") (pinfunction "PA1_45") (pintype "bidirectional"))
    )
    (net (code "46") (name "Net-(U1-PA2)") (class "Default")
      (node (ref "RB2") (pin "1") (pinfunction "1_1") (pintype "passive"))
      (node (ref "U1") (pin "46") (pinfunction "PA2_46") (pintype "bidirectional"))
    )
    (net (code "47") (name "Net-(U1-PA3)") (class "Default")
      (node (ref "RB1") (pin "1") (pinfunction "1_1") (pintype "passive"))
      (node (ref "U1") (pin "47") (pinfunction "PA3_47") (pintype "bidirectional"))
    )
    (net (code "48") (name "Net-(U1-PA4)") (class "Default")
      (node (ref "B7") (pin "1") (pinfunction "1_1") (pintype "passive"))
      (node (ref "RB26") (pin "1") (pinfunction "1_1") (pintype "passive"))
      (node (ref "U1") (pin "48") (pinfunction "PA4_48") (pintype "bidirectional"))
    )
    (net (code "49") (name "Net-(U1-PA5)") (class "Default")
      (node (ref "A7") (pin "1") (pinfunction "1_1") (pintype "passive"))
      (node (ref "RB27") (pin "1") (pinfunction "1_1") (pintype "passive"))
      (node (ref "U1") (pin "1") (pinfunction "PA5_1") (pintype "bidirectional"))
    )
    (net (code "50") (name "Net-(U1-PA6)") (class "Default")
      (node (ref "B4") (pin "1") (pinfunction "1_1") (pintype "passive"))
      (node (ref "RB28") (pin "1") (pinfunction "1_1") (pintype "passive"))
      (node (ref "U1") (pin "2") (pinfunction "PA6_2") (pintype "bidirectional"))
    )
    (net (code "51") (name "Net-(U1-PA7)") (class "Default")
      (node (ref "A4") (pin "1") (pinfunction "1_1") (pintype "passive"))
      (node (ref "RB29") (pin "1") (pinfunction "1_1") (pintype "passive"))
      (node (ref "U1") (pin "3") (pinfunction "PA7_3") (pintype "bidirectional"))
    )
    (net (code "52") (name "Net-(U1-PB0)") (class "Default")
      (node (ref "B3") (pin "1") (pinfunction "1_1") (pintype "passive"))
      (node (ref "RB30") (pin "1") (pinfunction "1_1") (pintype "passive"))
      (node (ref "U1") (pin "4") (pinfunction "PB0_4") (pintype "bidirectional"))
    )
    (net (code "53") (name "Net-(U1-PB1)") (class "Default")
      (node (ref "A3") (pin "1") (pinfunction "1_1") (pintype "passive"))
      (node (ref "RB31") (pin "1") (pinfunction "1_1") (pintype "passive"))
      (node (ref "U1") (pin "5") (pinfunction "PB1_5") (pintype "bidirectional"))
    )
    (net (code "54") (name "Net-(U1-PB4)") (class "Default")
      (node (ref "B2") (pin "1") (pinfunction "1_1") (pintype "passive"))
      (node (ref "RB32") (pin "1") (pinfunction "1_1") (pintype "passive"))
      (node (ref "U1") (pin "8") (pinfunction "PB4_8") (pintype "bidirectional"))
    )
    (net (code "55") (name "Net-(U1-PB5)") (class "Default")
      (node (ref "A2") (pin "1") (pinfunction "1_1") (pintype "passive"))
      (node (ref "RB33") (pin "1") (pinfunction "1_1") (pintype "passive"))
      (node (ref "U1") (pin "9") (pinfunction "PB5_9") (pintype "bidirectional"))
    )
    (net (code "56") (name "Net-(U1-PC0)") (class "Default")
      (node (ref "B1") (pin "1") (pinfunction "1_1") (pintype "passive"))
      (node (ref "RB34") (pin "1") (pinfunction "1_1") (pintype "passive"))
      (node (ref "U1") (pin "10") (pinfunction "PC0_10") (pintype "bidirectional"))
    )
    (net (code "57") (name "Net-(U1-PC1)") (class "Default")
      (node (ref "A1") (pin "1") (pinfunction "1_1") (pintype "passive"))
      (node (ref "RB35") (pin "1") (pinfunction "1_1") (pintype "passive"))
      (node (ref "U1") (pin "11") (pinfunction "PC1_11") (pintype "bidirectional"))
    )
    (net (code "58") (name "Net-(U1-PC2)") (class "Default")
      (node (ref "B6") (pin "1") (pinfunction "1_1") (pintype "passive"))
      (node (ref "RB36") (pin "1") (pinfunction "1_1") (pintype "passive"))
      (node (ref "U1") (pin "12") (pinfunction "PC2_12") (pintype "bidirectional"))
    )
    (net (code "59") (name "Net-(U1-PC3)") (class "Default")
      (node (ref "A6") (pin "1") (pinfunction "1_1") (pintype "passive"))
      (node (ref "RB37") (pin "1") (pinfunction "1_1") (pintype "passive"))
      (node (ref "U1") (pin "13") (pinfunction "PC3_13") (pintype "bidirectional"))
    )
    (net (code "60") (name "Net-(U1-PC4)") (class "Default")
      (node (ref "RB11") (pin "1") (pinfunction "1_1") (pintype "passive"))
      (node (ref "U1") (pin "16") (pinfunction "PC4_16") (pintype "bidirectional"))
    )
    (net (code "61") (name "Net-(U1-PC5)") (class "Default")
      (node (ref "RB3") (pin "1") (pinfunction "1_1") (pintype "passive"))
      (node (ref "U1") (pin "17") (pinfunction "PC5_17") (pintype "bidirectional"))
    )
    (net (code "62") (name "Net-(U1-PC6)") (class "Default")
      (node (ref "B5") (pin "1") (pinfunction "1_1") (pintype "passive"))
      (node (ref "RB44") (pin "1") (pinfunction "1_1") (pintype "passive"))
      (node (ref "U1") (pin "18") (pinfunction "PC6_18") (pintype "bidirectional"))
    )
    (net (code "63") (name "Net-(U1-PC7)") (class "Default")
      (node (ref "A5") (pin "1") (pinfunction "1_1") (pintype "passive"))
      (node (ref "RB45") (pin "1") (pinfunction "1_1") (pintype "passive"))
      (node (ref "U1") (pin "19") (pinfunction "PC7_19") (pintype "bidirectional"))
    )
    (net (code "64") (name "Net-(U1-PD0)") (class "Default")
      (node (ref "S5") (pin "1") (pinfunction "1_1") (pintype "passive"))
      (node (ref "S5") (pin "2") (pinfunction "1_2") (pintype "passive"))
      (node (ref "U1") (pin "20") (pinfunction "PD0_20") (pintype "bidirectional"))
    )
    (net (code "65") (name "Net-(U1-PD2)") (class "Default")
      (node (ref "RB19") (pin "2") (pinfunction "2_2") (pintype "passive"))
      (node (ref "U1") (pin "22") (pinfunction "PD2_22") (pintype "bidirectional"))
    )
    (net (code "66") (name "Net-(U1-PD3)") (class "Default")
      (node (ref "RB18") (pin "2") (pinfunction "2_2") (pintype "passive"))
      (node (ref "U1") (pin "23") (pinfunction "PD3_23") (pintype "bidirectional"))
    )
    (net (code "67") (name "Net-(U1-PD4)") (class "Default")
      (node (ref "A9") (pin "1") (pinfunction "1_1") (pintype "passive"))
      (node (ref "RB38") (pin "2") (pinfunction "2_2") (pintype "passive"))
      (node (ref "U1") (pin "24") (pinfunction "PD4_24") (pintype "bidirectional"))
    )
    (net (code "68") (name "Net-(U1-PD5)") (class "Default")
      (node (ref "B9") (pin "1") (pinfunction "1_1") (pintype "passive"))
      (node (ref "RB39") (pin "2") (pinfunction "2_2") (pintype "passive"))
      (node (ref "U1") (pin "25") (pinfunction "PD5_25") (pintype "bidirectional"))
    )
    (net (code "69") (name "Net-(U1-PD6)") (class "Default")
      (node (ref "A10") (pin "1") (pinfunction "1_1") (pintype "passive"))
      (node (ref "RB40") (pin "2") (pinfunction "2_2") (pintype "passive"))
      (node (ref "U1") (pin "26") (pinfunction "PD6_26") (pintype "bidirectional"))
    )
    (net (code "70") (name "Net-(U1-PD7)") (class "Default")
      (node (ref "B10") (pin "1") (pinfunction "1_1") (pintype "passive"))
      (node (ref "RB41") (pin "2") (pinfunction "2_2") (pintype "passive"))
      (node (ref "U1") (pin "27") (pinfunction "PD7_27") (pintype "bidirectional"))
    )
    (net (code "71") (name "Net-(U1-PE0)") (class "Default")
      (node (ref "RB0") (pin "2") (pinfunction "2_2") (pintype "passive"))
      (node (ref "U1") (pin "30") (pinfunction "PE0_30") (pintype "bidirectional"))
    )
    (net (code "72") (name "Net-(U1-PE1)") (class "Default")
      (node (ref "RB4") (pin "2") (pinfunction "2_2") (pintype "passive"))
      (node (ref "U1") (pin "31") (pinfunction "PE1_31") (pintype "bidirectional"))
    )
    (net (code "73") (name "Net-(U1-PE2)") (class "Default")
      (node (ref "RB5") (pin "2") (pinfunction "2_2") (pintype "passive"))
      (node (ref "U1") (pin "32") (pinfunction "PE2_32") (pintype "bidirectional"))
    )
    (net (code "74") (name "Net-(U1-PE3)") (class "Default")
      (node (ref "RB6") (pin "2") (pinfunction "2_2") (pintype "passive"))
      (node (ref "U1") (pin "33") (pinfunction "PE3_33") (pintype "bidirectional"))
    )
    (net (code "75") (name "Net-(U1-PF0)") (class "Default")
      (node (ref "A11") (pin "1") (pinfunction "1_1") (pintype "passive"))
      (node (ref "RB42") (pin "2") (pinfunction "2_2") (pintype "passive"))
      (node (ref "U1") (pin "34") (pinfunction "PF0_34") (pintype "bidirectional"))
    )
    (net (code "76") (name "Net-(U1-PF1)") (class "Default")
      (node (ref "A12") (pin "1") (pinfunction "1_1") (pintype "passive"))
      (node (ref "RB43") (pin "2") (pinfunction "2_2") (pintype "passive"))
      (node (ref "U1") (pin "35") (pinfunction "PF1_35") (pintype "bidirectional"))
    )
    (net (code "77") (name "Net-(U1-PF2)") (class "Default")
      (node (ref "RB7") (pin "2") (pinfunction "2_2") (pintype "passive"))
      (node (ref "U1") (pin "36") (pinfunction "PF2_36") (pintype "bidirectional"))
    )
    (net (code "78") (name "Net-(U1-PF3)") (class "Default")
      (node (ref "RB8") (pin "2") (pinfunction "2_2") (pintype "passive"))
      (node (ref "U1") (pin "37") (pinfunction "PF3_37") (pintype "bidirectional"))
    )
    (net (code "79") (name "VDD") (class "Default")
      (node (ref "C1") (pin "1") (pinfunction "1_1") (pintype "passive"))
      (node (ref "C2") (pin "1") (pinfunction "1_1") (pintype "passive"))
      (node (ref "C3") (pin "1") (pinfunction "1_1") (pintype "passive"))
      (node (ref "D1") (pin "C") (pinfunction "C_C") (pintype "passive"))
      (node (ref "JJ1") (pin "3") (pinfunction "3_3") (pintype "passive"))
      (node (ref "RB17") (pin "1") (pinfunction "1_1") (pintype "passive"))
      (node (ref "S1") (pin "3") (pinfunction "S_3") (pintype "passive"))
      (node (ref "S2") (pin "3") (pinfunction "S_3") (pintype "passive"))
      (node (ref "S3") (pin "3") (pinfunction "S_3") (pintype "passive"))
      (node (ref "S4") (pin "3") (pinfunction "S_3") (pintype "passive"))
      (node (ref "U1") (pin "14") (pinfunction "VDDIO2_14") (pintype "power_in"))
      (node (ref "U1") (pin "28") (pinfunction "AVDD_28") (pintype "power_in"))
      (node (ref "U1") (pin "42") (pinfunction "VDD_42") (pintype "power_in"))
    )
    (net (code "80") (name "unconnected-(OFF/ON-S-Pad3)") (class "Default")
      (node (ref "OFF/ON") (pin "3") (pinfunction "S_3") (pintype "passive"))
    )
    (net (code "81") (name "unconnected-(U1-PB2-Pad6)") (class "Default")
      (node (ref "U1") (pin "6") (pinfunction "PB2_6") (pintype "output"))
    )
    (net (code "82") (name "unconnected-(U1-PB3-Pad7)") (class "Default")
      (node (ref "U1") (pin "7") (pinfunction "PB3_7") (pintype "bidirectional"))
    )
    (net (code "83") (name "unconnected-(U1-PD1-Pad21)") (class "Default")
      (node (ref "U1") (pin "21") (pinfunction "PD1_21") (pintype "bidirectional"))
    )
    (net (code "84") (name "unconnected-(U1-PF4-Pad38)") (class "Default")
      (node (ref "U1") (pin "38") (pinfunction "PF4_38") (pintype "bidirectional"))
    )
    (net (code "85") (name "unconnected-(U1-PF5-Pad39)") (class "Default")
      (node (ref "U1") (pin "39") (pinfunction "PF5_39") (pintype "bidirectional"))
    )
    (net (code "86") (name "unconnected-(U1-PF6-Pad40)") (class "Default")
      (node (ref "U1") (pin "40") (pinfunction "PF6_40") (pintype "bidirectional"))
    )
  )
)
